# USB_DV_Stick_1V1_Sheet2.net
KiCad netlist of a schematic drawn in Altium Designer
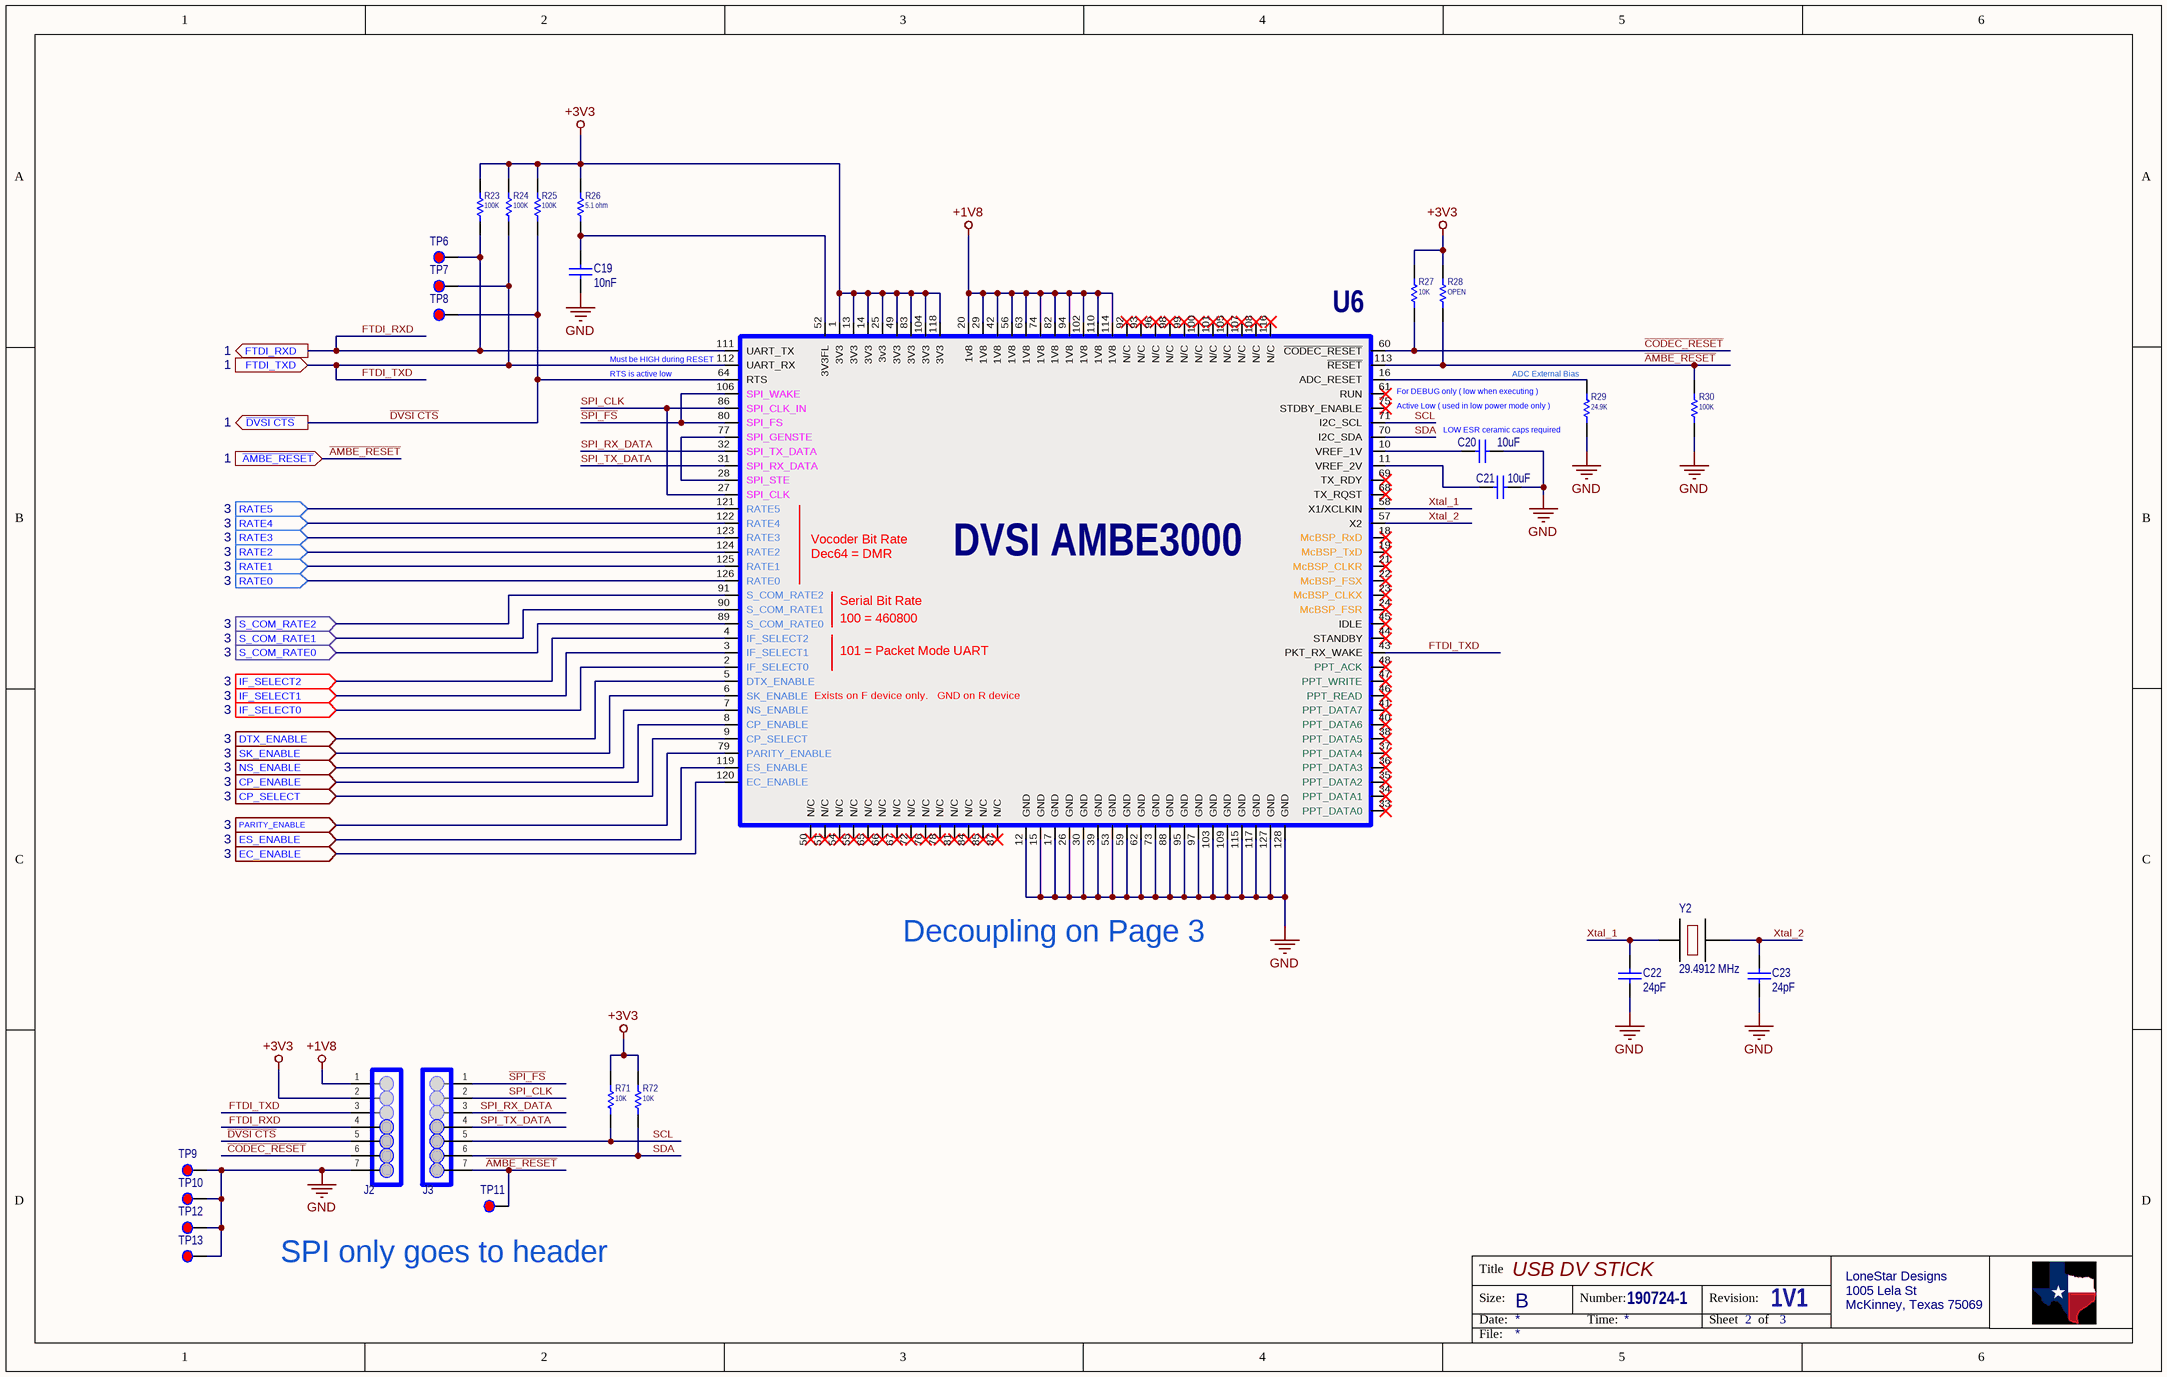
[diagram p0: USB DV Stick 1V1_Sheet2.SchDoc]

(export (version "E")
  (design (tool "Eeschema 10.0.6"))
  (components
    (comp (ref "C19")
      (value "10nF")
      (footprint "C0402")
      (description "Capacitor Surface Mount")
      (fields
        (field (name "MANUFACTURER") "Murata Electronics")
        (field (name "MANUFACTURER PART NUMBER") "GCM155R71H103KA55D")
      )
      (libsource (lib "Dave's") (part "Cap SM"))
    )
    (comp (ref "C20")
      (value "10uF")
      (footprint "C0805")
      (description "Capacitor Surface Mount")
      (fields
        (field (name "MANUFACTURER") "Murata Electronics")
        (field (name "MANUFACTURER PART NUMBER") "GRJ21BR61E106KE01K")
      )
      (libsource (lib "Dave's") (part "Cap SM"))
    )
    (comp (ref "C21")
      (value "10uF")
      (footprint "C0805")
      (description "Capacitor Surface Mount")
      (fields
        (field (name "MANUFACTURER") "Murata Electronics")
        (field (name "MANUFACTURER PART NUMBER") "GRJ21BR61E106KE01K")
      )
      (libsource (lib "Dave's") (part "Cap SM"))
    )
    (comp (ref "C22")
      (value "24pF")
      (footprint "C0402")
      (description "Capacitor Surface Mount")
      (fields
        (field (name "MANUFACTURER") "Murata Electronics")
        (field (name "MANUFACTURER PART NUMBER") "GCQ1555C1H240FB01D")
      )
      (libsource (lib "Dave's") (part "Cap SM"))
    )
    (comp (ref "C23")
      (value "24pF")
      (footprint "C0402")
      (description "Capacitor Surface Mount")
      (fields
        (field (name "MANUFACTURER") "Murata Electronics")
        (field (name "MANUFACTURER PART NUMBER") "GCQ1555C1H240FB01D")
      )
      (libsource (lib "Dave's") (part "Cap SM"))
    )
    (comp (ref "J2")
      (value "7x1 on 0.1\" centers")
      (footprint "HDR1x7")
      (libsource (lib "") (part "7x1 Pin Header_1"))
    )
    (comp (ref "J3")
      (value "7x1 on 0.1\" centers")
      (footprint "HDR1x7")
      (libsource (lib "Dave's Connector") (part "7x1 Pin Header"))
    )
    (comp (ref "R23")
      (value "100K")
      (footprint "R0603")
      (description "Resistor Surface Mount")
      (fields
        (field (name "MANUFACTURER") "Vishay / Dale")
        (field (name "MANUFACTURER PART NUMBER") "CRCW0603100KJNEAC")
      )
      (libsource (lib "Dave's") (part "RES SM"))
    )
    (comp (ref "R24")
      (value "100K")
      (footprint "R0603")
      (description "Resistor Surface Mount")
      (fields
        (field (name "MANUFACTURER") "Vishay / Dale")
        (field (name "MANUFACTURER PART NUMBER") "CRCW0603100KJNEAC")
      )
      (libsource (lib "Dave's") (part "RES SM"))
    )
    (comp (ref "R25")
      (value "100K")
      (footprint "R0603")
      (description "Resistor Surface Mount")
      (fields
        (field (name "MANUFACTURER") "Vishay / Dale")
        (field (name "MANUFACTURER PART NUMBER") "CRCW0603100KJNEAC")
      )
      (libsource (lib "Dave's") (part "RES SM"))
    )
    (comp (ref "R26")
      (value "5.1 ohm")
      (footprint "R0603")
      (description "Resistor Surface Mount")
      (fields
        (field (name "MANUFACTURER") "Vishay / Dale")
        (field (name "MANUFACTURER PART NUMBER") "RCS06035R10FKEA")
      )
      (libsource (lib "Dave's") (part "RES SM"))
    )
    (comp (ref "R27")
      (value "10K")
      (footprint "R0603")
      (description "Resistor Surface Mount")
      (fields
        (field (name "MANUFACTURER") "Vishay / Dale")
        (field (name "MANUFACTURER PART NUMBER") "CRCW060310K0FKEAC")
      )
      (libsource (lib "Dave's") (part "RES SM"))
    )
    (comp (ref "R28")
      (value "OPEN")
      (footprint "R0603")
      (description "Resistor Surface Mount")
      (libsource (lib "Dave's") (part "RES SM"))
    )
    (comp (ref "R29")
      (value "24.9K")
      (footprint "R0603")
      (description "Resistor Surface Mount")
      (fields
        (field (name "MANUFACTURER") "Vishay / Dale")
        (field (name "MANUFACTURER PART NUMBER") "CRCW060324K9FKEA")
      )
      (libsource (lib "Dave's") (part "RES SM"))
    )
    (comp (ref "R30")
      (value "100K")
      (footprint "R0603")
      (description "Resistor Surface Mount")
      (fields
        (field (name "MANUFACTURER") "Vishay / Dale")
        (field (name "MANUFACTURER PART NUMBER") "CRCW0603100KJNEAC")
      )
      (libsource (lib "Dave's") (part "RES SM"))
    )
    (comp (ref "R71")
      (value "10K")
      (footprint "R0402")
      (description "Resistor Surface Mount")
      (fields
        (field (name "MANUFACTURER") "Vishay / Dale")
        (field (name "MANUFACTURER PART NUMBER") "CRCW060310K0FKEAC")
      )
      (libsource (lib "Dave's") (part "RES SM"))
    )
    (comp (ref "R72")
      (value "10K")
      (footprint "R0402")
      (description "Resistor Surface Mount")
      (fields
        (field (name "MANUFACTURER") "Vishay / Dale")
        (field (name "MANUFACTURER PART NUMBER") "CRCW060310K0FKEAC")
      )
      (libsource (lib "Dave's") (part "RES SM"))
    )
    (comp (ref "TP6")
      (value "5015")
      (footprint "Dave's:TP SM")
      (description "Surface Mount")
      (fields (field (name "MANUFACTURER") "Keystone"))
      (libsource (lib "Dave's") (part "Test Point"))
    )
    (comp (ref "TP7")
      (value "5015")
      (footprint "Dave's:TP SM")
      (description "Surface Mount")
      (fields (field (name "MANUFACTURER") "Keystone"))
      (libsource (lib "Dave's") (part "Test Point"))
    )
    (comp (ref "TP8")
      (value "5015")
      (footprint "Dave's:TP SM")
      (description "Surface Mount")
      (fields (field (name "MANUFACTURER") "Keystone"))
      (libsource (lib "Dave's") (part "Test Point"))
    )
    (comp (ref "TP9")
      (value "5015")
      (footprint "Dave's:TP SM")
      (description "Surface Mount")
      (fields (field (name "MANUFACTURER") "Keystone"))
      (libsource (lib "Dave's") (part "Test Point"))
    )
    (comp (ref "TP10")
      (value "5015")
      (footprint "Dave's:TP SM")
      (description "Surface Mount")
      (fields (field (name "MANUFACTURER") "Keystone"))
      (libsource (lib "Dave's") (part "Test Point"))
    )
    (comp (ref "TP11")
      (value "5015")
      (footprint "Dave's:TP SM")
      (description "Surface Mount")
      (fields (field (name "MANUFACTURER") "Keystone"))
      (libsource (lib "Dave's") (part "Test Point"))
    )
    (comp (ref "TP12")
      (value "5015")
      (footprint "Dave's:TP SM")
      (description "Surface Mount")
      (fields (field (name "MANUFACTURER") "Keystone"))
      (libsource (lib "Dave's") (part "Test Point"))
    )
    (comp (ref "TP13")
      (value "5015")
      (footprint "Dave's:TP SM")
      (description "Surface Mount")
      (fields (field (name "MANUFACTURER") "Keystone"))
      (libsource (lib "Dave's") (part "Test Point"))
    )
    (comp (ref "U6")
      (value "DVSI AMBE3000")
      (footprint "LQFP-128")
      (description "AMBE vocoder ( Logical Pin Order )")
      (fields (field (name "MANUFACTURER") "DVSI") (field (name "MANUFACTURER PART NUMBER") "AMBE3000R"))
      (libsource (lib "Dave's Silicon") (part "AMBE3000F_Pin_Modified"))
    )
    (comp (ref "Y2")
      (value "29.4912 MHz")
      (footprint "Xtal 5.0x3.2")
      (description "Surface Mount Crystal  ( 5.0 x 3.2 )")
      (fields
        (field (name "MANUFACTURER PART NUMBER") "ABM3-29.4912MHZ-B4Y-T")
        (field (name "MANUFACTURER") "ABRACON")
      )
      (libsource (lib "Dave's") (part "Xtal"))
    )
  )
  (nets
    (net (code "1") (name "+1V8") (class "Default")
      (node (ref "J2") (pin "1") (pinfunction "1_1") (pintype "passive"))
      (node (ref "U6") (pin "102") (pinfunction "1V8_102") (pintype "passive"))
      (node (ref "U6") (pin "110") (pinfunction "1V8_110") (pintype "passive"))
      (node (ref "U6") (pin "114") (pinfunction "1V8_114") (pintype "passive"))
      (node (ref "U6") (pin "20") (pinfunction "1v8_20") (pintype "passive"))
      (node (ref "U6") (pin "29") (pinfunction "1V8_29") (pintype "passive"))
      (node (ref "U6") (pin "42") (pinfunction "1V8_42") (pintype "passive"))
      (node (ref "U6") (pin "56") (pinfunction "1V8_56") (pintype "passive"))
      (node (ref "U6") (pin "63") (pinfunction "1V8_63") (pintype "passive"))
      (node (ref "U6") (pin "74") (pinfunction "1V8_74") (pintype "passive"))
      (node (ref "U6") (pin "82") (pinfunction "1V8_82") (pintype "passive"))
      (node (ref "U6") (pin "94") (pinfunction "1V8_94") (pintype "passive"))
    )
    (net (code "2") (name "+3V3") (class "Default")
      (node (ref "J2") (pin "2") (pinfunction "2_2") (pintype "passive"))
      (node (ref "R23") (pin "2") (pinfunction "2_2") (pintype "passive"))
      (node (ref "R24") (pin "2") (pinfunction "2_2") (pintype "passive"))
      (node (ref "R25") (pin "2") (pinfunction "2_2") (pintype "passive"))
      (node (ref "R26") (pin "2") (pinfunction "2_2") (pintype "passive"))
      (node (ref "R27") (pin "2") (pinfunction "2_2") (pintype "passive"))
      (node (ref "R28") (pin "2") (pinfunction "2_2") (pintype "passive"))
      (node (ref "R71") (pin "2") (pinfunction "2_2") (pintype "passive"))
      (node (ref "R72") (pin "2") (pinfunction "2_2") (pintype "passive"))
      (node (ref "U6") (pin "1") (pinfunction "3V3_1") (pintype "passive"))
      (node (ref "U6") (pin "104") (pinfunction "3V3_104") (pintype "passive"))
      (node (ref "U6") (pin "118") (pinfunction "3V3_118") (pintype "passive"))
      (node (ref "U6") (pin "13") (pinfunction "3V3_13") (pintype "passive"))
      (node (ref "U6") (pin "14") (pinfunction "3V3_14") (pintype "passive"))
      (node (ref "U6") (pin "25") (pinfunction "3v3_25") (pintype "passive"))
      (node (ref "U6") (pin "49") (pinfunction "3V3_49") (pintype "passive"))
      (node (ref "U6") (pin "83") (pinfunction "3V3_83") (pintype "passive"))
    )
    (net (code "3") (name "/CP_ENABLE") (class "Default")
      (node (ref "U6") (pin "8") (pinfunction "CP_ENABLE_8") (pintype "passive"))
    )
    (net (code "4") (name "/CP_SELECT") (class "Default")
      (node (ref "U6") (pin "9") (pinfunction "CP_SELECT_9") (pintype "passive"))
    )
    (net (code "5") (name "/DTX_ENABLE") (class "Default")
      (node (ref "U6") (pin "5") (pinfunction "DTX_ENABLE_5") (pintype "passive"))
    )
    (net (code "6") (name "/EC_ENABLE") (class "Default")
      (node (ref "U6") (pin "120") (pinfunction "EC_ENABLE_120") (pintype "passive"))
    )
    (net (code "7") (name "/ES_ENABLE") (class "Default")
      (node (ref "U6") (pin "119") (pinfunction "ES_ENABLE_119") (pintype "passive"))
    )
    (net (code "8") (name "/FTDI_RXD") (class "Default")
      (node (ref "J2") (pin "4") (pinfunction "4_4") (pintype "passive"))
      (node (ref "R23") (pin "1") (pinfunction "1_1") (pintype "passive"))
      (node (ref "TP6") (pin "1") (pintype "passive"))
      (node (ref "U6") (pin "111") (pinfunction "UART_TX_111") (pintype "passive"))
    )
    (net (code "9") (name "/FTDI_TXD") (class "Default")
      (node (ref "J2") (pin "3") (pinfunction "3_3") (pintype "passive"))
      (node (ref "R24") (pin "1") (pinfunction "1_1") (pintype "passive"))
      (node (ref "TP7") (pin "1") (pintype "passive"))
      (node (ref "U6") (pin "112") (pinfunction "UART_RX_112") (pintype "passive"))
      (node (ref "U6") (pin "43") (pinfunction "PKT_RX_WAKE_43") (pintype "passive"))
    )
    (net (code "10") (name "/IF_SELECT0") (class "Default")
      (node (ref "U6") (pin "2") (pinfunction "IF_SELECT0_2") (pintype "passive"))
    )
    (net (code "11") (name "/IF_SELECT1") (class "Default")
      (node (ref "U6") (pin "3") (pinfunction "IF_SELECT1_3") (pintype "passive"))
    )
    (net (code "12") (name "/IF_SELECT2") (class "Default")
      (node (ref "U6") (pin "4") (pinfunction "IF_SELECT2_4") (pintype "passive"))
    )
    (net (code "13") (name "/NS_ENABLE") (class "Default")
      (node (ref "U6") (pin "7") (pinfunction "NS_ENABLE_7") (pintype "passive"))
    )
    (net (code "14") (name "/PARITY_ENABLE") (class "Default")
      (node (ref "U6") (pin "79") (pinfunction "PARITY_ENABLE_79") (pintype "passive"))
    )
    (net (code "15") (name "/RATE0") (class "Default")
      (node (ref "U6") (pin "126") (pinfunction "RATE0_126") (pintype "passive"))
    )
    (net (code "16") (name "/RATE1") (class "Default")
      (node (ref "U6") (pin "125") (pinfunction "RATE1_125") (pintype "passive"))
    )
    (net (code "17") (name "/RATE2") (class "Default")
      (node (ref "U6") (pin "124") (pinfunction "RATE2_124") (pintype "passive"))
    )
    (net (code "18") (name "/RATE3") (class "Default")
      (node (ref "U6") (pin "123") (pinfunction "RATE3_123") (pintype "passive"))
    )
    (net (code "19") (name "/RATE4") (class "Default")
      (node (ref "U6") (pin "122") (pinfunction "RATE4_122") (pintype "passive"))
    )
    (net (code "20") (name "/RATE5") (class "Default")
      (node (ref "U6") (pin "121") (pinfunction "RATE5_121") (pintype "passive"))
    )
    (net (code "21") (name "/SCL") (class "Default")
      (node (ref "J3") (pin "5") (pinfunction "5_5") (pintype "passive"))
      (node (ref "R71") (pin "1") (pinfunction "1_1") (pintype "passive"))
      (node (ref "U6") (pin "71") (pinfunction "I2C_SCL_71") (pintype "passive"))
    )
    (net (code "22") (name "/SDA") (class "Default")
      (node (ref "J3") (pin "6") (pinfunction "6_6") (pintype "passive"))
      (node (ref "R72") (pin "1") (pinfunction "1_1") (pintype "passive"))
      (node (ref "U6") (pin "70") (pinfunction "I2C_SDA_70") (pintype "passive"))
    )
    (net (code "23") (name "/SK_ENABLE") (class "Default")
      (node (ref "U6") (pin "6") (pinfunction "SK_ENABLE_6") (pintype "passive"))
    )
    (net (code "24") (name "/SPI_CLK") (class "Default")
      (node (ref "J3") (pin "2") (pinfunction "2_2") (pintype "passive"))
      (node (ref "U6") (pin "27") (pinfunction "SPI_CLK_27") (pintype "passive"))
      (node (ref "U6") (pin "86") (pinfunction "SPI_CLK_IN_86") (pintype "passive"))
    )
    (net (code "25") (name "/SPI_RX_DATA") (class "Default")
      (node (ref "J3") (pin "3") (pinfunction "3_3") (pintype "passive"))
      (node (ref "U6") (pin "32") (pinfunction "SPI_TX_DATA_32") (pintype "passive"))
    )
    (net (code "26") (name "/SPI_TX_DATA") (class "Default")
      (node (ref "J3") (pin "4") (pinfunction "4_4") (pintype "passive"))
      (node (ref "U6") (pin "31") (pinfunction "SPI_RX_DATA_31") (pintype "passive"))
    )
    (net (code "27") (name "/S_COM_RATE0") (class "Default")
      (node (ref "U6") (pin "89") (pinfunction "S_COM_RATE0_89") (pintype "passive"))
    )
    (net (code "28") (name "/S_COM_RATE1") (class "Default")
      (node (ref "U6") (pin "90") (pinfunction "S_COM_RATE1_90") (pintype "passive"))
    )
    (net (code "29") (name "/S_COM_RATE2") (class "Default")
      (node (ref "U6") (pin "91") (pinfunction "S_COM_RATE2_91") (pintype "passive"))
    )
    (net (code "30") (name "/Xtal_1") (class "Default")
      (node (ref "C22") (pin "2") (pinfunction "2_2") (pintype "passive"))
      (node (ref "U6") (pin "58") (pinfunction "X1/XCLKIN_58") (pintype "passive"))
      (node (ref "Y2") (pin "1") (pinfunction "1_1") (pintype "passive"))
    )
    (net (code "31") (name "/Xtal_2") (class "Default")
      (node (ref "C23") (pin "2") (pinfunction "2_2") (pintype "passive"))
      (node (ref "U6") (pin "57") (pinfunction "X2_57") (pintype "passive"))
      (node (ref "Y2") (pin "2") (pinfunction "2_2") (pintype "passive"))
    )
    (net (code "32") (name "/~{AMBE_RESET}") (class "Default")
      (node (ref "J3") (pin "7") (pinfunction "7_7") (pintype "passive"))
      (node (ref "R28") (pin "1") (pinfunction "1_1") (pintype "passive"))
      (node (ref "R30") (pin "2") (pinfunction "2_2") (pintype "passive"))
      (node (ref "TP11") (pin "1") (pintype "passive"))
      (node (ref "U6") (pin "113") (pinfunction "~{RESET}_113") (pintype "passive"))
    )
    (net (code "33") (name "/~{CODEC_RESET}") (class "Default")
      (node (ref "J2") (pin "6") (pinfunction "6_6") (pintype "passive"))
      (node (ref "R27") (pin "1") (pinfunction "1_1") (pintype "passive"))
      (node (ref "U6") (pin "60") (pinfunction "~{CODEC_RESET}_60") (pintype "passive"))
    )
    (net (code "34") (name "/~{DVSI CTS}") (class "Default")
      (node (ref "J2") (pin "5") (pinfunction "5_5") (pintype "passive"))
      (node (ref "R25") (pin "1") (pinfunction "1_1") (pintype "passive"))
      (node (ref "TP8") (pin "1") (pintype "passive"))
      (node (ref "U6") (pin "64") (pinfunction "RTS_64") (pintype "passive"))
    )
    (net (code "35") (name "/~{SPI_FS}") (class "Default")
      (node (ref "J3") (pin "1") (pinfunction "1_1") (pintype "passive"))
      (node (ref "U6") (pin "106") (pinfunction "SPI_WAKE_106") (pintype "passive"))
      (node (ref "U6") (pin "80") (pinfunction "SPI_FS_80") (pintype "passive"))
    )
    (net (code "36") (name "GND") (class "Default")
      (node (ref "C19") (pin "1") (pinfunction "1_1") (pintype "passive"))
      (node (ref "C20") (pin "2") (pinfunction "2_2") (pintype "passive"))
      (node (ref "C21") (pin "2") (pinfunction "2_2") (pintype "passive"))
      (node (ref "C22") (pin "1") (pinfunction "1_1") (pintype "passive"))
      (node (ref "C23") (pin "1") (pinfunction "1_1") (pintype "passive"))
      (node (ref "J2") (pin "7") (pinfunction "7_7") (pintype "passive"))
      (node (ref "R29") (pin "1") (pinfunction "1_1") (pintype "passive"))
      (node (ref "R30") (pin "1") (pinfunction "1_1") (pintype "passive"))
      (node (ref "TP10") (pin "1") (pintype "passive"))
      (node (ref "TP12") (pin "1") (pintype "passive"))
      (node (ref "TP13") (pin "1") (pintype "passive"))
      (node (ref "TP9") (pin "1") (pintype "passive"))
      (node (ref "U6") (pin "103") (pinfunction "GND_103") (pintype "passive"))
      (node (ref "U6") (pin "109") (pinfunction "GND_109") (pintype "passive"))
      (node (ref "U6") (pin "115") (pinfunction "GND_115") (pintype "passive"))
      (node (ref "U6") (pin "117") (pinfunction "GND_117") (pintype "passive"))
      (node (ref "U6") (pin "12") (pinfunction "GND_12") (pintype "passive"))
      (node (ref "U6") (pin "127") (pinfunction "GND_127") (pintype "passive"))
      (node (ref "U6") (pin "128") (pinfunction "GND_128") (pintype "passive"))
      (node (ref "U6") (pin "15") (pinfunction "GND_15") (pintype "passive"))
      (node (ref "U6") (pin "17") (pinfunction "GND_17") (pintype "passive"))
      (node (ref "U6") (pin "26") (pinfunction "GND_26") (pintype "passive"))
      (node (ref "U6") (pin "30") (pinfunction "GND_30") (pintype "passive"))
      (node (ref "U6") (pin "39") (pinfunction "GND_39") (pintype "passive"))
      (node (ref "U6") (pin "53") (pinfunction "GND_53") (pintype "passive"))
      (node (ref "U6") (pin "59") (pinfunction "GND_59") (pintype "passive"))
      (node (ref "U6") (pin "62") (pinfunction "GND_62") (pintype "passive"))
      (node (ref "U6") (pin "73") (pinfunction "GND_73") (pintype "passive"))
      (node (ref "U6") (pin "88") (pinfunction "GND_88") (pintype "passive"))
      (node (ref "U6") (pin "95") (pinfunction "GND_95") (pintype "passive"))
      (node (ref "U6") (pin "97") (pinfunction "GND_97") (pintype "passive"))
    )
    (net (code "37") (name "Net-(U6-3V3FL)") (class "Default")
      (node (ref "C19") (pin "2") (pinfunction "2_2") (pintype "passive"))
      (node (ref "R26") (pin "1") (pinfunction "1_1") (pintype "passive"))
      (node (ref "U6") (pin "52") (pinfunction "3V3FL_52") (pintype "passive"))
    )
    (net (code "38") (name "Net-(U6-ADC_RESET)") (class "Default")
      (node (ref "R29") (pin "2") (pinfunction "2_2") (pintype "passive"))
      (node (ref "U6") (pin "16") (pinfunction "ADC_RESET_16") (pintype "passive"))
    )
    (net (code "39") (name "Net-(U6-SPI_GENSTE)") (class "Default")
      (node (ref "U6") (pin "28") (pinfunction "SPI_STE_28") (pintype "passive"))
      (node (ref "U6") (pin "77") (pinfunction "SPI_GENSTE_77") (pintype "passive"))
    )
    (net (code "40") (name "Net-(U6-VREF_1V)") (class "Default")
      (node (ref "C20") (pin "1") (pinfunction "1_1") (pintype "passive"))
      (node (ref "U6") (pin "10") (pinfunction "VREF_1V_10") (pintype "passive"))
    )
    (net (code "41") (name "Net-(U6-VREF_2V)") (class "Default")
      (node (ref "C21") (pin "1") (pinfunction "1_1") (pintype "passive"))
      (node (ref "U6") (pin "11") (pinfunction "VREF_2V_11") (pintype "passive"))
    )
    (net (code "42") (name "unconnected-(U6-IDLE-Pad45)") (class "Default")
      (node (ref "U6") (pin "45") (pinfunction "IDLE_45") (pintype "passive+no_connect"))
    )
    (net (code "43") (name "unconnected-(U6-McBSP_CLKR-Pad21)") (class "Default")
      (node (ref "U6") (pin "21") (pinfunction "McBSP_CLKR_21") (pintype "passive+no_connect"))
    )
    (net (code "44") (name "unconnected-(U6-McBSP_CLKX-Pad23)") (class "Default")
      (node (ref "U6") (pin "23") (pinfunction "McBSP_CLKX_23") (pintype "passive+no_connect"))
    )
    (net (code "45") (name "unconnected-(U6-McBSP_FSR-Pad24)") (class "Default")
      (node (ref "U6") (pin "24") (pinfunction "McBSP_FSR_24") (pintype "passive+no_connect"))
    )
    (net (code "46") (name "unconnected-(U6-McBSP_FSX-Pad22)") (class "Default")
      (node (ref "U6") (pin "22") (pinfunction "McBSP_FSX_22") (pintype "passive+no_connect"))
    )
    (net (code "47") (name "unconnected-(U6-McBSP_RxD-Pad18)") (class "Default")
      (node (ref "U6") (pin "18") (pinfunction "McBSP_RxD_18") (pintype "passive+no_connect"))
    )
    (net (code "48") (name "unconnected-(U6-McBSP_TxD-Pad19)") (class "Default")
      (node (ref "U6") (pin "19") (pinfunction "McBSP_TxD_19") (pintype "passive+no_connect"))
    )
    (net (code "49") (name "unconnected-(U6-N{slash}C-Pad50)") (class "Default")
      (node (ref "U6") (pin "50") (pinfunction "N/C_50") (pintype "passive+no_connect"))
    )
    (net (code "50") (name "unconnected-(U6-N{slash}C-Pad51)") (class "Default")
      (node (ref "U6") (pin "51") (pinfunction "N/C_51") (pintype "passive+no_connect"))
    )
    (net (code "51") (name "unconnected-(U6-N{slash}C-Pad54)") (class "Default")
      (node (ref "U6") (pin "54") (pinfunction "N/C_54") (pintype "passive+no_connect"))
    )
    (net (code "52") (name "unconnected-(U6-N{slash}C-Pad55)") (class "Default")
      (node (ref "U6") (pin "55") (pinfunction "N/C_55") (pintype "passive+no_connect"))
    )
    (net (code "53") (name "unconnected-(U6-N{slash}C-Pad65)") (class "Default")
      (node (ref "U6") (pin "65") (pinfunction "N/C_65") (pintype "passive+no_connect"))
    )
    (net (code "54") (name "unconnected-(U6-N{slash}C-Pad66)") (class "Default")
      (node (ref "U6") (pin "66") (pinfunction "N/C_66") (pintype "passive+no_connect"))
    )
    (net (code "55") (name "unconnected-(U6-N{slash}C-Pad67)") (class "Default")
      (node (ref "U6") (pin "67") (pinfunction "N/C_67") (pintype "passive+no_connect"))
    )
    (net (code "56") (name "unconnected-(U6-N{slash}C-Pad72)") (class "Default")
      (node (ref "U6") (pin "72") (pinfunction "N/C_72") (pintype "passive+no_connect"))
    )
    (net (code "57") (name "unconnected-(U6-N{slash}C-Pad76)") (class "Default")
      (node (ref "U6") (pin "76") (pinfunction "N/C_76") (pintype "passive+no_connect"))
    )
    (net (code "58") (name "unconnected-(U6-N{slash}C-Pad78)") (class "Default")
      (node (ref "U6") (pin "78") (pinfunction "N/C_78") (pintype "passive+no_connect"))
    )
    (net (code "59") (name "unconnected-(U6-N{slash}C-Pad81)") (class "Default")
      (node (ref "U6") (pin "81") (pinfunction "N/C_81") (pintype "passive+no_connect"))
    )
    (net (code "60") (name "unconnected-(U6-N{slash}C-Pad84)") (class "Default")
      (node (ref "U6") (pin "84") (pinfunction "N/C_84") (pintype "passive+no_connect"))
    )
    (net (code "61") (name "unconnected-(U6-N{slash}C-Pad85)") (class "Default")
      (node (ref "U6") (pin "85") (pinfunction "N/C_85") (pintype "passive+no_connect"))
    )
    (net (code "62") (name "unconnected-(U6-N{slash}C-Pad87)") (class "Default")
      (node (ref "U6") (pin "87") (pinfunction "N/C_87") (pintype "passive+no_connect"))
    )
    (net (code "63") (name "unconnected-(U6-N{slash}C-Pad92)") (class "Default")
      (node (ref "U6") (pin "92") (pinfunction "N/C_92") (pintype "passive+no_connect"))
    )
    (net (code "64") (name "unconnected-(U6-N{slash}C-Pad93)") (class "Default")
      (node (ref "U6") (pin "93") (pinfunction "N/C_93") (pintype "passive+no_connect"))
    )
    (net (code "65") (name "unconnected-(U6-N{slash}C-Pad96)") (class "Default")
      (node (ref "U6") (pin "96") (pinfunction "N/C_96") (pintype "passive+no_connect"))
    )
    (net (code "66") (name "unconnected-(U6-N{slash}C-Pad98)") (class "Default")
      (node (ref "U6") (pin "98") (pinfunction "N/C_98") (pintype "passive+no_connect"))
    )
    (net (code "67") (name "unconnected-(U6-N{slash}C-Pad99)") (class "Default")
      (node (ref "U6") (pin "99") (pinfunction "N/C_99") (pintype "passive+no_connect"))
    )
    (net (code "68") (name "unconnected-(U6-N{slash}C-Pad100)") (class "Default")
      (node (ref "U6") (pin "100") (pinfunction "N/C_100") (pintype "passive+no_connect"))
    )
    (net (code "69") (name "unconnected-(U6-N{slash}C-Pad101)") (class "Default")
      (node (ref "U6") (pin "101") (pinfunction "N/C_101") (pintype "passive+no_connect"))
    )
    (net (code "70") (name "unconnected-(U6-N{slash}C-Pad105)") (class "Default")
      (node (ref "U6") (pin "105") (pinfunction "N/C_105") (pintype "passive+no_connect"))
    )
    (net (code "71") (name "unconnected-(U6-N{slash}C-Pad107)") (class "Default")
      (node (ref "U6") (pin "107") (pinfunction "N/C_107") (pintype "passive+no_connect"))
    )
    (net (code "72") (name "unconnected-(U6-N{slash}C-Pad108)") (class "Default")
      (node (ref "U6") (pin "108") (pinfunction "N/C_108") (pintype "passive+no_connect"))
    )
    (net (code "73") (name "unconnected-(U6-N{slash}C-Pad116)") (class "Default")
      (node (ref "U6") (pin "116") (pinfunction "N/C_116") (pintype "passive+no_connect"))
    )
    (net (code "74") (name "unconnected-(U6-PPT_ACK-Pad48)") (class "Default")
      (node (ref "U6") (pin "48") (pinfunction "PPT_ACK_48") (pintype "passive+no_connect"))
    )
    (net (code "75") (name "unconnected-(U6-PPT_DATA0-Pad33)") (class "Default")
      (node (ref "U6") (pin "33") (pinfunction "PPT_DATA0_33") (pintype "passive+no_connect"))
    )
    (net (code "76") (name "unconnected-(U6-PPT_DATA1-Pad34)") (class "Default")
      (node (ref "U6") (pin "34") (pinfunction "PPT_DATA1_34") (pintype "passive+no_connect"))
    )
    (net (code "77") (name "unconnected-(U6-PPT_DATA2-Pad35)") (class "Default")
      (node (ref "U6") (pin "35") (pinfunction "PPT_DATA2_35") (pintype "passive+no_connect"))
    )
    (net (code "78") (name "unconnected-(U6-PPT_DATA3-Pad36)") (class "Default")
      (node (ref "U6") (pin "36") (pinfunction "PPT_DATA3_36") (pintype "passive+no_connect"))
    )
    (net (code "79") (name "unconnected-(U6-PPT_DATA4-Pad37)") (class "Default")
      (node (ref "U6") (pin "37") (pinfunction "PPT_DATA4_37") (pintype "passive+no_connect"))
    )
    (net (code "80") (name "unconnected-(U6-PPT_DATA5-Pad38)") (class "Default")
      (node (ref "U6") (pin "38") (pinfunction "PPT_DATA5_38") (pintype "passive+no_connect"))
    )
    (net (code "81") (name "unconnected-(U6-PPT_DATA6-Pad40)") (class "Default")
      (node (ref "U6") (pin "40") (pinfunction "PPT_DATA6_40") (pintype "passive+no_connect"))
    )
    (net (code "82") (name "unconnected-(U6-PPT_DATA7-Pad41)") (class "Default")
      (node (ref "U6") (pin "41") (pinfunction "PPT_DATA7_41") (pintype "passive+no_connect"))
    )
    (net (code "83") (name "unconnected-(U6-PPT_READ-Pad46)") (class "Default")
      (node (ref "U6") (pin "46") (pinfunction "PPT_READ_46") (pintype "passive+no_connect"))
    )
    (net (code "84") (name "unconnected-(U6-PPT_WRITE-Pad47)") (class "Default")
      (node (ref "U6") (pin "47") (pinfunction "PPT_WRITE_47") (pintype "passive+no_connect"))
    )
    (net (code "85") (name "unconnected-(U6-RUN-Pad61)") (class "Default")
      (node (ref "U6") (pin "61") (pinfunction "RUN_61") (pintype "passive+no_connect"))
    )
    (net (code "86") (name "unconnected-(U6-STANDBY-Pad44)") (class "Default")
      (node (ref "U6") (pin "44") (pinfunction "STANDBY_44") (pintype "passive+no_connect"))
    )
    (net (code "87") (name "unconnected-(U6-STDBY_ENABLE-Pad75)") (class "Default")
      (node (ref "U6") (pin "75") (pinfunction "STDBY_ENABLE_75") (pintype "passive+no_connect"))
    )
    (net (code "88") (name "unconnected-(U6-TX_RDY-Pad69)") (class "Default")
      (node (ref "U6") (pin "69") (pinfunction "TX_RDY_69") (pintype "passive+no_connect"))
    )
    (net (code "89") (name "unconnected-(U6-TX_RQST-Pad68)") (class "Default")
      (node (ref "U6") (pin "68") (pinfunction "TX_RQST_68") (pintype "passive+no_connect"))
    )
  )
)
